# Sheet1.net
KiCad netlist of a schematic drawn in Altium Designer
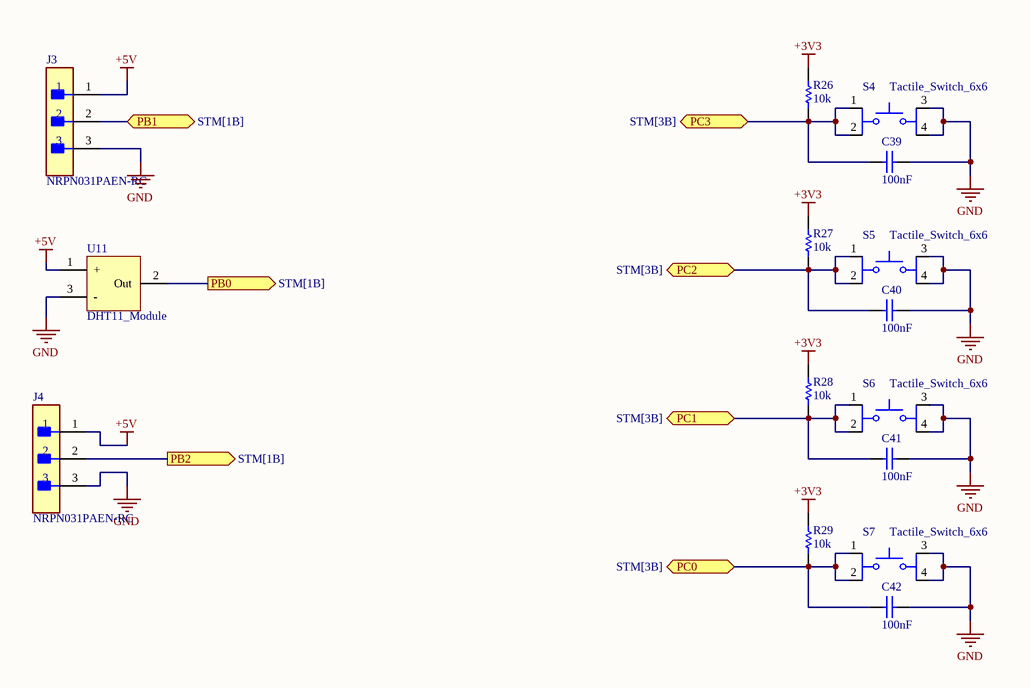
[diagram p0: Sheet1.SchDoc]

(export (version "E")
  (design (tool "Eeschema 10.0.6"))
  (components
    (comp (ref "C39")
      (value "100nF")
      (footprint "CAP_0603")
      (description "CAP, size 0603, 100nF")
      (libsource (lib "SMIOT_Lib_Schematic") (part "01060310410"))
    )
    (comp (ref "C40")
      (value "100nF")
      (footprint "CAP_0603")
      (description "CAP, size 0603, 100nF")
      (libsource (lib "SMIOT_Lib_Schematic") (part "01060310410"))
    )
    (comp (ref "C41")
      (value "100nF")
      (footprint "CAP_0603")
      (description "CAP, size 0603, 100nF")
      (libsource (lib "SMIOT_Lib_Schematic") (part "01060310410"))
    )
    (comp (ref "C42")
      (value "100nF")
      (footprint "CAP_0603")
      (description "CAP, size 0603, 100nF")
      (libsource (lib "SMIOT_Lib_Schematic") (part "01060310410"))
    )
    (comp (ref "J3")
      (value "NRPN031PAEN-RC")
      (footprint "FP-NRPN031PAEN-RC-MFG")
      (description "Male, 3 C, Straight, .079\"CC; 3.60mm Head/2.80mm Tail, No Mt; Nylon 6-T, Brass, 105 C")
      (libsource (lib "University of Technology") (part "0d3f023dd272f625e17a2be33dea85f"))
    )
    (comp (ref "J4")
      (value "NRPN031PAEN-RC")
      (footprint "FP-NRPN031PAEN-RC-MFG")
      (description "Male, 3 C, Straight, .079\"CC; 3.60mm Head/2.80mm Tail, No Mt; Nylon 6-T, Brass, 105 C")
      (libsource (lib "University of Technology") (part "0d3f023dd272f625e17a2be33dea85f"))
    )
    (comp (ref "R26")
      (value "10k")
      (footprint "resistor_0603")
      (description "RES, 10k Ohm, size 0603, 1%")
      (libsource (lib "SMIOT_Lib_Schematic") (part "0006031031"))
    )
    (comp (ref "R27")
      (value "10k")
      (footprint "resistor_0603")
      (description "RES, 10k Ohm, size 0603, 1%")
      (libsource (lib "SMIOT_Lib_Schematic") (part "0006031031"))
    )
    (comp (ref "R28")
      (value "10k")
      (footprint "resistor_0603")
      (description "RES, 10k Ohm, size 0603, 1%")
      (libsource (lib "SMIOT_Lib_Schematic") (part "0006031031"))
    )
    (comp (ref "R29")
      (value "10k")
      (footprint "resistor_0603")
      (description "RES, 10k Ohm, size 0603, 1%")
      (libsource (lib "SMIOT_Lib_Schematic") (part "0006031031"))
    )
    (comp (ref "S4")
      (value "Tactile_Switch_6x6")
      (footprint "Tactile_Switch_6x6")
      (description "Tactile Switch, 6x6mm")
      (libsource (lib "SMIOT_Lib_Schematic") (part "Tactile_Switch_6x6"))
    )
    (comp (ref "S5")
      (value "Tactile_Switch_6x6")
      (footprint "Tactile_Switch_6x6")
      (description "Tactile Switch, 6x6mm")
      (libsource (lib "SMIOT_Lib_Schematic") (part "Tactile_Switch_6x6"))
    )
    (comp (ref "S6")
      (value "Tactile_Switch_6x6")
      (footprint "Tactile_Switch_6x6")
      (description "Tactile Switch, 6x6mm")
      (libsource (lib "SMIOT_Lib_Schematic") (part "Tactile_Switch_6x6"))
    )
    (comp (ref "S7")
      (value "Tactile_Switch_6x6")
      (footprint "Tactile_Switch_6x6")
      (description "Tactile Switch, 6x6mm")
      (libsource (lib "SMIOT_Lib_Schematic") (part "Tactile_Switch_6x6"))
    )
    (comp (ref "U11")
      (value "DHT11_Module")
      (footprint "DHT11_Module")
      (description "Temperature & Humidity Sensor, 3.3V-5V, 5mA")
      (libsource (lib "SMIOT_Lib_Schematic") (part "DHT11_Module"))
    )
  )
  (nets
    (net (code "1") (name "+3V3") (class "Default")
      (node (ref "R26") (pin "1") (pinfunction "1_1") (pintype "passive"))
      (node (ref "R27") (pin "1") (pinfunction "1_1") (pintype "passive"))
      (node (ref "R28") (pin "1") (pinfunction "1_1") (pintype "passive"))
      (node (ref "R29") (pin "1") (pinfunction "1_1") (pintype "passive"))
    )
    (net (code "2") (name "+5V") (class "Default")
      (node (ref "J3") (pin "1") (pinfunction "1_1") (pintype "passive"))
      (node (ref "J4") (pin "1") (pinfunction "1_1") (pintype "passive"))
      (node (ref "U11") (pin "1") (pinfunction "+_1") (pintype "passive"))
    )
    (net (code "3") (name "/PB0") (class "Default")
      (node (ref "U11") (pin "2") (pinfunction "Out_2") (pintype "passive"))
    )
    (net (code "4") (name "/PB1") (class "Default")
      (node (ref "J3") (pin "2") (pinfunction "2_2") (pintype "passive"))
    )
    (net (code "5") (name "/PB2") (class "Default")
      (node (ref "J4") (pin "2") (pinfunction "2_2") (pintype "passive"))
    )
    (net (code "6") (name "/PC0") (class "Default")
      (node (ref "C42") (pin "1") (pinfunction "1_1") (pintype "passive"))
      (node (ref "R29") (pin "2") (pinfunction "2_2") (pintype "passive"))
      (node (ref "S7") (pin "1") (pinfunction "1_1") (pintype "passive"))
      (node (ref "S7") (pin "2") (pinfunction "2_2") (pintype "passive"))
    )
    (net (code "7") (name "/PC1") (class "Default")
      (node (ref "C41") (pin "1") (pinfunction "1_1") (pintype "passive"))
      (node (ref "R28") (pin "2") (pinfunction "2_2") (pintype "passive"))
      (node (ref "S6") (pin "1") (pinfunction "1_1") (pintype "passive"))
      (node (ref "S6") (pin "2") (pinfunction "2_2") (pintype "passive"))
    )
    (net (code "8") (name "/PC2") (class "Default")
      (node (ref "C40") (pin "1") (pinfunction "1_1") (pintype "passive"))
      (node (ref "R27") (pin "2") (pinfunction "2_2") (pintype "passive"))
      (node (ref "S5") (pin "1") (pinfunction "1_1") (pintype "passive"))
      (node (ref "S5") (pin "2") (pinfunction "2_2") (pintype "passive"))
    )
    (net (code "9") (name "/PC3") (class "Default")
      (node (ref "C39") (pin "1") (pinfunction "1_1") (pintype "passive"))
      (node (ref "R26") (pin "2") (pinfunction "2_2") (pintype "passive"))
      (node (ref "S4") (pin "1") (pinfunction "1_1") (pintype "passive"))
      (node (ref "S4") (pin "2") (pinfunction "2_2") (pintype "passive"))
    )
    (net (code "10") (name "GND") (class "Default")
      (node (ref "C39") (pin "2") (pinfunction "2_2") (pintype "passive"))
      (node (ref "C40") (pin "2") (pinfunction "2_2") (pintype "passive"))
      (node (ref "C41") (pin "2") (pinfunction "2_2") (pintype "passive"))
      (node (ref "C42") (pin "2") (pinfunction "2_2") (pintype "passive"))
      (node (ref "J3") (pin "3") (pinfunction "3_3") (pintype "passive"))
      (node (ref "J4") (pin "3") (pinfunction "3_3") (pintype "passive"))
      (node (ref "S4") (pin "3") (pinfunction "3_3") (pintype "passive"))
      (node (ref "S4") (pin "4") (pinfunction "4_4") (pintype "passive"))
      (node (ref "S5") (pin "3") (pinfunction "3_3") (pintype "passive"))
      (node (ref "S5") (pin "4") (pinfunction "4_4") (pintype "passive"))
      (node (ref "S6") (pin "3") (pinfunction "3_3") (pintype "passive"))
      (node (ref "S6") (pin "4") (pinfunction "4_4") (pintype "passive"))
      (node (ref "S7") (pin "3") (pinfunction "3_3") (pintype "passive"))
      (node (ref "S7") (pin "4") (pinfunction "4_4") (pintype "passive"))
      (node (ref "U11") (pin "3") (pinfunction "-_3") (pintype "power_in"))
    )
  )
)
